# inputs.net
KiCad netlist of a schematic drawn in Altium Designer
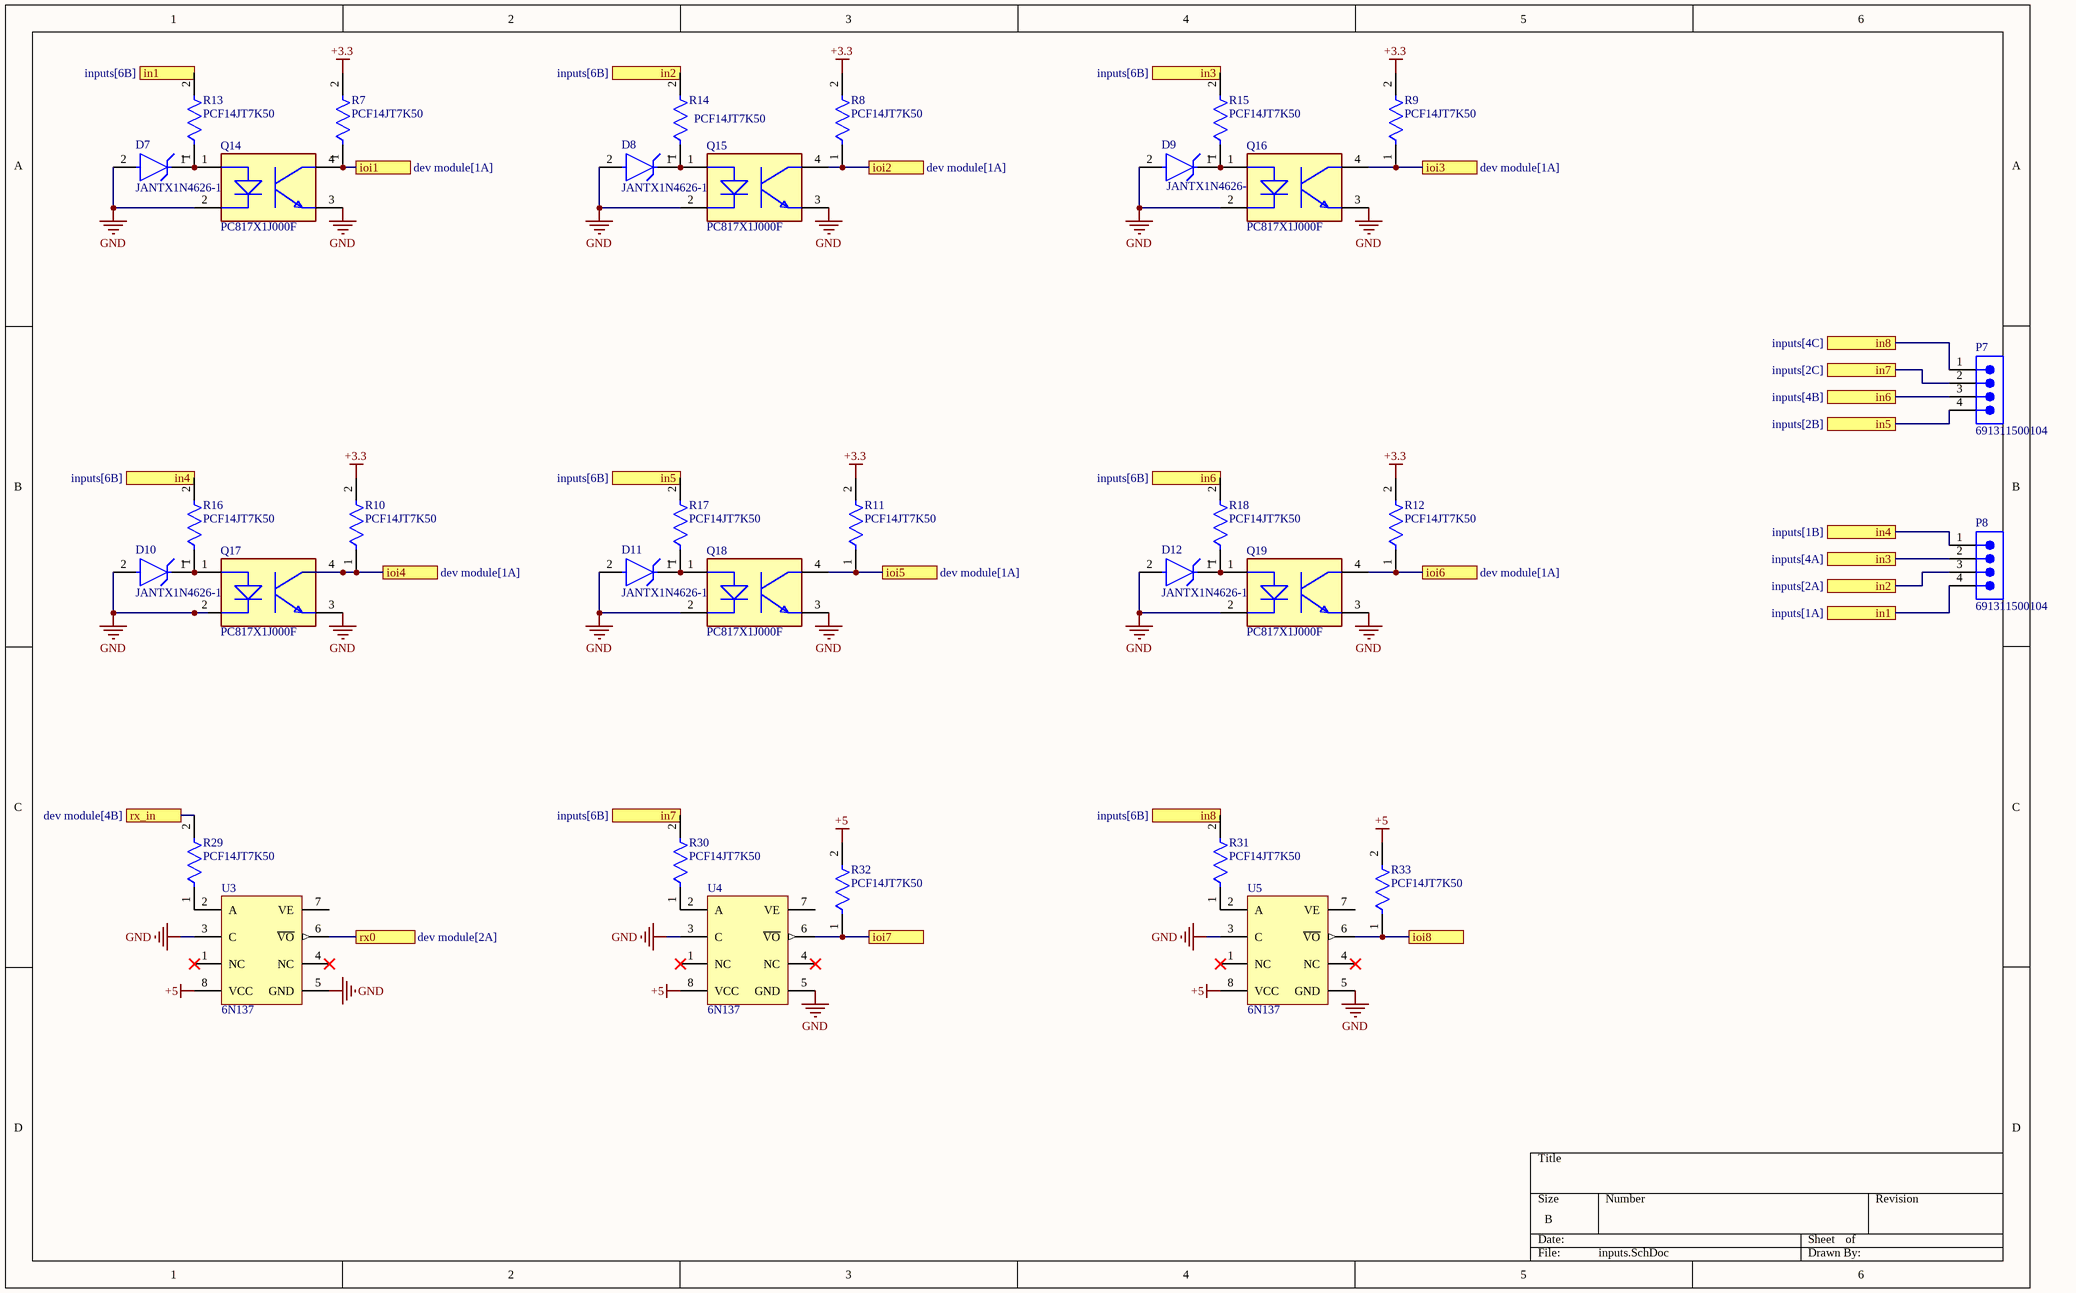
[diagram p0: inputs.SchDoc]

(export (version "E")
  (design (tool "Eeschema 10.0.6"))
  (components
    (comp (ref "D7")
      (value "JANTX1N4626-1")
      (footprint "FP-DO-35-MFG")
      (description "JANTX1N4626-1 Metallurgically Bonded Glass Zener Diode 5.6V 500mW 5% 2-Pin DO-204AH")
      (fields (field (name "TOLERANCE") "5%"))
      (libsource (lib "Altium Content Vault") (part "f813f71cba58e380607f5dd3caf9714"))
    )
    (comp (ref "D8")
      (value "JANTX1N4626-1")
      (footprint "FP-DO-35-MFG")
      (description "JANTX1N4626-1 Metallurgically Bonded Glass Zener Diode 5.6V 500mW 5% 2-Pin DO-204AH")
      (fields (field (name "TOLERANCE") "5%"))
      (libsource (lib "Altium Content Vault") (part "f813f71cba58e380607f5dd3caf9714"))
    )
    (comp (ref "D9")
      (value "JANTX1N4626-1")
      (footprint "FP-DO-35-MFG")
      (description "JANTX1N4626-1 Metallurgically Bonded Glass Zener Diode 5.6V 500mW 5% 2-Pin DO-204AH")
      (fields (field (name "TOLERANCE") "5%"))
      (libsource (lib "Altium Content Vault") (part "f813f71cba58e380607f5dd3caf9714"))
    )
    (comp (ref "D10")
      (value "JANTX1N4626-1")
      (footprint "FP-DO-35-MFG")
      (description "JANTX1N4626-1 Metallurgically Bonded Glass Zener Diode 5.6V 500mW 5% 2-Pin DO-204AH")
      (fields (field (name "TOLERANCE") "5%"))
      (libsource (lib "Altium Content Vault") (part "f813f71cba58e380607f5dd3caf9714"))
    )
    (comp (ref "D11")
      (value "JANTX1N4626-1")
      (footprint "FP-DO-35-MFG")
      (description "JANTX1N4626-1 Metallurgically Bonded Glass Zener Diode 5.6V 500mW 5% 2-Pin DO-204AH")
      (fields (field (name "TOLERANCE") "5%"))
      (libsource (lib "Altium Content Vault") (part "f813f71cba58e380607f5dd3caf9714"))
    )
    (comp (ref "D12")
      (value "JANTX1N4626-1")
      (footprint "FP-DO-35-MFG")
      (description "JANTX1N4626-1 Metallurgically Bonded Glass Zener Diode 5.6V 500mW 5% 2-Pin DO-204AH")
      (fields (field (name "TOLERANCE") "5%"))
      (libsource (lib "Altium Content Vault") (part "f813f71cba58e380607f5dd3caf9714"))
    )
    (comp (ref "P7")
      (value "691311500104")
      (footprint "691311500104")
      (fields (field (name "VOLTAGE") "300V"))
      (libsource (lib "Altium Content Vault") (part "TBL - 1R - 04P - Male"))
    )
    (comp (ref "P8")
      (value "691311500104")
      (footprint "691311500104")
      (fields (field (name "VOLTAGE") "300V"))
      (libsource (lib "Altium Content Vault") (part "TBL - 1R - 04P - Male"))
    )
    (comp (ref "Q14")
      (value "PC817X1J000F")
      (footprint "FP-PC817X1J000F-MFG")
      (description "OPTOISOLATOR 5KV TRANS 4DIP")
      (libsource (lib "Altium Content Vault") (part "8d9d817270a4e8f0d794346117f6aa3"))
    )
    (comp (ref "Q15")
      (value "PC817X1J000F")
      (footprint "FP-PC817X1J000F-MFG")
      (description "OPTOISOLATOR 5KV TRANS 4DIP")
      (libsource (lib "Altium Content Vault") (part "8d9d817270a4e8f0d794346117f6aa3"))
    )
    (comp (ref "Q16")
      (value "PC817X1J000F")
      (footprint "FP-PC817X1J000F-MFG")
      (description "OPTOISOLATOR 5KV TRANS 4DIP")
      (libsource (lib "Altium Content Vault") (part "8d9d817270a4e8f0d794346117f6aa3"))
    )
    (comp (ref "Q17")
      (value "PC817X1J000F")
      (footprint "FP-PC817X1J000F-MFG")
      (description "OPTOISOLATOR 5KV TRANS 4DIP")
      (libsource (lib "Altium Content Vault") (part "8d9d817270a4e8f0d794346117f6aa3"))
    )
    (comp (ref "Q18")
      (value "PC817X1J000F")
      (footprint "FP-PC817X1J000F-MFG")
      (description "OPTOISOLATOR 5KV TRANS 4DIP")
      (libsource (lib "Altium Content Vault") (part "8d9d817270a4e8f0d794346117f6aa3"))
    )
    (comp (ref "Q19")
      (value "PC817X1J000F")
      (footprint "FP-PC817X1J000F-MFG")
      (description "OPTOISOLATOR 5KV TRANS 4DIP")
      (libsource (lib "Altium Content Vault") (part "8d9d817270a4e8f0d794346117f6aa3"))
    )
    (comp (ref "R7")
      (value "PCF14JT7K50")
      (footprint "FP-CF14-MFG")
      (description "RES 7.5K OHM 1/4W 5% AXIAL")
      (fields (field (name "TOLERANCE") "5%"))
      (libsource (lib "Altium Content Vault") (part "1029c3af85768c4190bb7ad29bc67b5"))
    )
    (comp (ref "R8")
      (value "PCF14JT7K50")
      (footprint "FP-CF14-MFG")
      (description "RES 7.5K OHM 1/4W 5% AXIAL")
      (fields (field (name "TOLERANCE") "5%"))
      (libsource (lib "Altium Content Vault") (part "1029c3af85768c4190bb7ad29bc67b5"))
    )
    (comp (ref "R9")
      (value "PCF14JT7K50")
      (footprint "FP-CF14-MFG")
      (description "RES 7.5K OHM 1/4W 5% AXIAL")
      (fields (field (name "TOLERANCE") "5%"))
      (libsource (lib "Altium Content Vault") (part "1029c3af85768c4190bb7ad29bc67b5"))
    )
    (comp (ref "R10")
      (value "PCF14JT7K50")
      (footprint "FP-CF14-MFG")
      (description "RES 7.5K OHM 1/4W 5% AXIAL")
      (fields (field (name "TOLERANCE") "5%"))
      (libsource (lib "Altium Content Vault") (part "1029c3af85768c4190bb7ad29bc67b5"))
    )
    (comp (ref "R11")
      (value "PCF14JT7K50")
      (footprint "FP-CF14-MFG")
      (description "RES 7.5K OHM 1/4W 5% AXIAL")
      (fields (field (name "TOLERANCE") "5%"))
      (libsource (lib "Altium Content Vault") (part "1029c3af85768c4190bb7ad29bc67b5"))
    )
    (comp (ref "R12")
      (value "PCF14JT7K50")
      (footprint "FP-CF14-MFG")
      (description "RES 7.5K OHM 1/4W 5% AXIAL")
      (fields (field (name "TOLERANCE") "5%"))
      (libsource (lib "Altium Content Vault") (part "1029c3af85768c4190bb7ad29bc67b5"))
    )
    (comp (ref "R13")
      (value "PCF14JT7K50")
      (footprint "FP-CF14-MFG")
      (description "RES 7.5K OHM 1/4W 5% AXIAL")
      (fields (field (name "TOLERANCE") "5%"))
      (libsource (lib "Altium Content Vault") (part "1029c3af85768c4190bb7ad29bc67b5"))
    )
    (comp (ref "R14")
      (value "PCF14JT7K50")
      (footprint "FP-CF14-MFG")
      (description "RES 7.5K OHM 1/4W 5% AXIAL")
      (fields (field (name "TOLERANCE") "5%"))
      (libsource (lib "Altium Content Vault") (part "1029c3af85768c4190bb7ad29bc67b5"))
    )
    (comp (ref "R15")
      (value "PCF14JT7K50")
      (footprint "FP-CF14-MFG")
      (description "RES 7.5K OHM 1/4W 5% AXIAL")
      (fields (field (name "TOLERANCE") "5%"))
      (libsource (lib "Altium Content Vault") (part "1029c3af85768c4190bb7ad29bc67b5"))
    )
    (comp (ref "R16")
      (value "PCF14JT7K50")
      (footprint "FP-CF14-MFG")
      (description "RES 7.5K OHM 1/4W 5% AXIAL")
      (fields (field (name "TOLERANCE") "5%"))
      (libsource (lib "Altium Content Vault") (part "1029c3af85768c4190bb7ad29bc67b5"))
    )
    (comp (ref "R17")
      (value "PCF14JT7K50")
      (footprint "FP-CF14-MFG")
      (description "RES 7.5K OHM 1/4W 5% AXIAL")
      (fields (field (name "TOLERANCE") "5%"))
      (libsource (lib "Altium Content Vault") (part "1029c3af85768c4190bb7ad29bc67b5"))
    )
    (comp (ref "R18")
      (value "PCF14JT7K50")
      (footprint "FP-CF14-MFG")
      (description "RES 7.5K OHM 1/4W 5% AXIAL")
      (fields (field (name "TOLERANCE") "5%"))
      (libsource (lib "Altium Content Vault") (part "1029c3af85768c4190bb7ad29bc67b5"))
    )
    (comp (ref "R29")
      (value "PCF14JT7K50")
      (footprint "FP-CF14-MFG")
      (description "RES 7.5K OHM 1/4W 5% AXIAL")
      (fields (field (name "TOLERANCE") "5%"))
      (libsource (lib "Altium Content Vault") (part "1029c3af85768c4190bb7ad29bc67b5"))
    )
    (comp (ref "R30")
      (value "PCF14JT7K50")
      (footprint "FP-CF14-MFG")
      (description "RES 7.5K OHM 1/4W 5% AXIAL")
      (fields (field (name "TOLERANCE") "5%"))
      (libsource (lib "Altium Content Vault") (part "1029c3af85768c4190bb7ad29bc67b5"))
    )
    (comp (ref "R31")
      (value "PCF14JT7K50")
      (footprint "FP-CF14-MFG")
      (description "RES 7.5K OHM 1/4W 5% AXIAL")
      (fields (field (name "TOLERANCE") "5%"))
      (libsource (lib "Altium Content Vault") (part "1029c3af85768c4190bb7ad29bc67b5"))
    )
    (comp (ref "R32")
      (value "PCF14JT7K50")
      (footprint "FP-CF14-MFG")
      (description "RES 7.5K OHM 1/4W 5% AXIAL")
      (fields (field (name "TOLERANCE") "5%"))
      (libsource (lib "Altium Content Vault") (part "1029c3af85768c4190bb7ad29bc67b5"))
    )
    (comp (ref "R33")
      (value "PCF14JT7K50")
      (footprint "FP-CF14-MFG")
      (description "RES 7.5K OHM 1/4W 5% AXIAL")
      (fields (field (name "TOLERANCE") "5%"))
      (libsource (lib "Altium Content Vault") (part "1029c3af85768c4190bb7ad29bc67b5"))
    )
    (comp (ref "U3")
      (value "6N137")
      (footprint "VISH-DIP-8_A")
      (description "High Speed Optocoupler, Single and Dual, 10 MBd, 5 V, -40 to 100 degC, 8-Pin DIP, RoHS, Tube")
      (fields (field (name "MANUFACTURER") "Vishay"))
      (libsource (lib "Altium Content Vault") (part "VISH-6N137-DIP-8"))
    )
    (comp (ref "U4")
      (value "6N137")
      (footprint "VISH-DIP-8_A")
      (description "High Speed Optocoupler, Single and Dual, 10 MBd, 5 V, -40 to 100 degC, 8-Pin DIP, RoHS, Tube")
      (fields (field (name "MANUFACTURER") "Vishay"))
      (libsource (lib "Altium Content Vault") (part "VISH-6N137-DIP-8"))
    )
    (comp (ref "U5")
      (value "6N137")
      (footprint "VISH-DIP-8_A")
      (description "High Speed Optocoupler, Single and Dual, 10 MBd, 5 V, -40 to 100 degC, 8-Pin DIP, RoHS, Tube")
      (fields (field (name "MANUFACTURER") "Vishay"))
      (libsource (lib "Altium Content Vault") (part "VISH-6N137-DIP-8"))
    )
  )
  (nets
    (net (code "1") (name "+3.3") (class "Default")
      (node (ref "R10") (pin "2") (pinfunction "2_2") (pintype "passive"))
      (node (ref "R11") (pin "2") (pinfunction "2_2") (pintype "passive"))
      (node (ref "R12") (pin "2") (pinfunction "2_2") (pintype "passive"))
      (node (ref "R7") (pin "2") (pinfunction "2_2") (pintype "passive"))
      (node (ref "R8") (pin "2") (pinfunction "2_2") (pintype "passive"))
      (node (ref "R9") (pin "2") (pinfunction "2_2") (pintype "passive"))
    )
    (net (code "2") (name "+5") (class "Default")
      (node (ref "R32") (pin "2") (pinfunction "2_2") (pintype "passive"))
      (node (ref "R33") (pin "2") (pinfunction "2_2") (pintype "passive"))
      (node (ref "U3") (pin "8") (pinfunction "VCC_8") (pintype "power_in"))
      (node (ref "U4") (pin "8") (pinfunction "VCC_8") (pintype "power_in"))
      (node (ref "U5") (pin "8") (pinfunction "VCC_8") (pintype "power_in"))
    )
    (net (code "3") (name "/in1") (class "Default")
      (node (ref "P8") (pin "4") (pinfunction "4_4") (pintype "passive"))
      (node (ref "R13") (pin "2") (pinfunction "2_2") (pintype "passive"))
    )
    (net (code "4") (name "/in2") (class "Default")
      (node (ref "P8") (pin "3") (pinfunction "3_3") (pintype "passive"))
      (node (ref "R14") (pin "2") (pinfunction "2_2") (pintype "passive"))
    )
    (net (code "5") (name "/in3") (class "Default")
      (node (ref "P8") (pin "2") (pinfunction "2_2") (pintype "passive"))
      (node (ref "R15") (pin "2") (pinfunction "2_2") (pintype "passive"))
    )
    (net (code "6") (name "/in4") (class "Default")
      (node (ref "P8") (pin "1") (pinfunction "1_1") (pintype "passive"))
      (node (ref "R16") (pin "2") (pinfunction "2_2") (pintype "passive"))
    )
    (net (code "7") (name "/in5") (class "Default")
      (node (ref "P7") (pin "4") (pinfunction "4_4") (pintype "passive"))
      (node (ref "R17") (pin "2") (pinfunction "2_2") (pintype "passive"))
    )
    (net (code "8") (name "/in6") (class "Default")
      (node (ref "P7") (pin "3") (pinfunction "3_3") (pintype "passive"))
      (node (ref "R18") (pin "2") (pinfunction "2_2") (pintype "passive"))
    )
    (net (code "9") (name "/in7") (class "Default")
      (node (ref "P7") (pin "2") (pinfunction "2_2") (pintype "passive"))
      (node (ref "R30") (pin "2") (pinfunction "2_2") (pintype "passive"))
    )
    (net (code "10") (name "/in8") (class "Default")
      (node (ref "P7") (pin "1") (pinfunction "1_1") (pintype "passive"))
      (node (ref "R31") (pin "2") (pinfunction "2_2") (pintype "passive"))
    )
    (net (code "11") (name "/ioi1") (class "Default")
      (node (ref "Q14") (pin "4") (pinfunction "C_4") (pintype "passive"))
      (node (ref "R7") (pin "1") (pinfunction "1_1") (pintype "passive"))
    )
    (net (code "12") (name "/ioi2") (class "Default")
      (node (ref "Q15") (pin "4") (pinfunction "C_4") (pintype "passive"))
      (node (ref "R8") (pin "1") (pinfunction "1_1") (pintype "passive"))
    )
    (net (code "13") (name "/ioi3") (class "Default")
      (node (ref "Q16") (pin "4") (pinfunction "C_4") (pintype "passive"))
      (node (ref "R9") (pin "1") (pinfunction "1_1") (pintype "passive"))
    )
    (net (code "14") (name "/ioi4") (class "Default")
      (node (ref "Q17") (pin "4") (pinfunction "C_4") (pintype "passive"))
      (node (ref "R10") (pin "1") (pinfunction "1_1") (pintype "passive"))
    )
    (net (code "15") (name "/ioi5") (class "Default")
      (node (ref "Q18") (pin "4") (pinfunction "C_4") (pintype "passive"))
      (node (ref "R11") (pin "1") (pinfunction "1_1") (pintype "passive"))
    )
    (net (code "16") (name "/ioi6") (class "Default")
      (node (ref "Q19") (pin "4") (pinfunction "C_4") (pintype "passive"))
      (node (ref "R12") (pin "1") (pinfunction "1_1") (pintype "passive"))
    )
    (net (code "17") (name "/ioi7") (class "Default")
      (node (ref "R32") (pin "1") (pinfunction "1_1") (pintype "passive"))
      (node (ref "U4") (pin "6") (pinfunction "~{VO}_6") (pintype "output"))
    )
    (net (code "18") (name "/ioi8") (class "Default")
      (node (ref "R33") (pin "1") (pinfunction "1_1") (pintype "passive"))
      (node (ref "U5") (pin "6") (pinfunction "~{VO}_6") (pintype "output"))
    )
    (net (code "19") (name "/rx0") (class "Default")
      (node (ref "U3") (pin "6") (pinfunction "~{VO}_6") (pintype "output"))
    )
    (net (code "20") (name "/rx_in") (class "Default")
      (node (ref "R29") (pin "2") (pinfunction "2_2") (pintype "passive"))
    )
    (net (code "21") (name "GND") (class "Default")
      (node (ref "D10") (pin "2") (pinfunction "A_2") (pintype "passive"))
      (node (ref "D11") (pin "2") (pinfunction "A_2") (pintype "passive"))
      (node (ref "D12") (pin "2") (pinfunction "A_2") (pintype "passive"))
      (node (ref "D7") (pin "2") (pinfunction "A_2") (pintype "passive"))
      (node (ref "D8") (pin "2") (pinfunction "A_2") (pintype "passive"))
      (node (ref "D9") (pin "2") (pinfunction "A_2") (pintype "passive"))
      (node (ref "Q14") (pin "2") (pinfunction "C_2") (pintype "passive"))
      (node (ref "Q14") (pin "3") (pinfunction "E_3") (pintype "passive"))
      (node (ref "Q15") (pin "2") (pinfunction "C_2") (pintype "passive"))
      (node (ref "Q15") (pin "3") (pinfunction "E_3") (pintype "passive"))
      (node (ref "Q16") (pin "2") (pinfunction "C_2") (pintype "passive"))
      (node (ref "Q16") (pin "3") (pinfunction "E_3") (pintype "passive"))
      (node (ref "Q17") (pin "2") (pinfunction "C_2") (pintype "passive"))
      (node (ref "Q17") (pin "3") (pinfunction "E_3") (pintype "passive"))
      (node (ref "Q18") (pin "2") (pinfunction "C_2") (pintype "passive"))
      (node (ref "Q18") (pin "3") (pinfunction "E_3") (pintype "passive"))
      (node (ref "Q19") (pin "2") (pinfunction "C_2") (pintype "passive"))
      (node (ref "Q19") (pin "3") (pinfunction "E_3") (pintype "passive"))
      (node (ref "U3") (pin "3") (pinfunction "C_3") (pintype "passive"))
      (node (ref "U3") (pin "5") (pinfunction "GND_5") (pintype "power_in"))
      (node (ref "U4") (pin "3") (pinfunction "C_3") (pintype "passive"))
      (node (ref "U4") (pin "5") (pinfunction "GND_5") (pintype "power_in"))
      (node (ref "U5") (pin "3") (pinfunction "C_3") (pintype "passive"))
      (node (ref "U5") (pin "5") (pinfunction "GND_5") (pintype "power_in"))
    )
    (net (code "22") (name "Net-(D7-C)") (class "Default")
      (node (ref "D7") (pin "1") (pinfunction "C_1") (pintype "passive"))
      (node (ref "Q14") (pin "1") (pinfunction "A_1") (pintype "passive"))
      (node (ref "R13") (pin "1") (pinfunction "1_1") (pintype "passive"))
    )
    (net (code "23") (name "Net-(D8-C)") (class "Default")
      (node (ref "D8") (pin "1") (pinfunction "C_1") (pintype "passive"))
      (node (ref "Q15") (pin "1") (pinfunction "A_1") (pintype "passive"))
      (node (ref "R14") (pin "1") (pinfunction "1_1") (pintype "passive"))
    )
    (net (code "24") (name "Net-(D9-C)") (class "Default")
      (node (ref "D9") (pin "1") (pinfunction "C_1") (pintype "passive"))
      (node (ref "Q16") (pin "1") (pinfunction "A_1") (pintype "passive"))
      (node (ref "R15") (pin "1") (pinfunction "1_1") (pintype "passive"))
    )
    (net (code "25") (name "Net-(D10-C)") (class "Default")
      (node (ref "D10") (pin "1") (pinfunction "C_1") (pintype "passive"))
      (node (ref "Q17") (pin "1") (pinfunction "A_1") (pintype "passive"))
      (node (ref "R16") (pin "1") (pinfunction "1_1") (pintype "passive"))
    )
    (net (code "26") (name "Net-(D11-C)") (class "Default")
      (node (ref "D11") (pin "1") (pinfunction "C_1") (pintype "passive"))
      (node (ref "Q18") (pin "1") (pinfunction "A_1") (pintype "passive"))
      (node (ref "R17") (pin "1") (pinfunction "1_1") (pintype "passive"))
    )
    (net (code "27") (name "Net-(D12-C)") (class "Default")
      (node (ref "D12") (pin "1") (pinfunction "C_1") (pintype "passive"))
      (node (ref "Q19") (pin "1") (pinfunction "A_1") (pintype "passive"))
      (node (ref "R18") (pin "1") (pinfunction "1_1") (pintype "passive"))
    )
    (net (code "28") (name "Net-(U3-A)") (class "Default")
      (node (ref "R29") (pin "1") (pinfunction "1_1") (pintype "passive"))
      (node (ref "U3") (pin "2") (pinfunction "A_2") (pintype "passive"))
    )
    (net (code "29") (name "Net-(U4-A)") (class "Default")
      (node (ref "R30") (pin "1") (pinfunction "1_1") (pintype "passive"))
      (node (ref "U4") (pin "2") (pinfunction "A_2") (pintype "passive"))
    )
    (net (code "30") (name "Net-(U5-A)") (class "Default")
      (node (ref "R31") (pin "1") (pinfunction "1_1") (pintype "passive"))
      (node (ref "U5") (pin "2") (pinfunction "A_2") (pintype "passive"))
    )
    (net (code "31") (name "unconnected-(U3-NC-Pad1)") (class "Default")
      (node (ref "U3") (pin "1") (pinfunction "NC_1") (pintype "passive+no_connect"))
    )
    (net (code "32") (name "unconnected-(U3-NC-Pad4)") (class "Default")
      (node (ref "U3") (pin "4") (pinfunction "NC_4") (pintype "passive+no_connect"))
    )
    (net (code "33") (name "unconnected-(U3-VE-Pad7)") (class "Default")
      (node (ref "U3") (pin "7") (pinfunction "VE_7") (pintype "power_in"))
    )
    (net (code "34") (name "unconnected-(U4-NC-Pad1)") (class "Default")
      (node (ref "U4") (pin "1") (pinfunction "NC_1") (pintype "passive+no_connect"))
    )
    (net (code "35") (name "unconnected-(U4-NC-Pad4)") (class "Default")
      (node (ref "U4") (pin "4") (pinfunction "NC_4") (pintype "passive+no_connect"))
    )
    (net (code "36") (name "unconnected-(U4-VE-Pad7)") (class "Default")
      (node (ref "U4") (pin "7") (pinfunction "VE_7") (pintype "power_in"))
    )
    (net (code "37") (name "unconnected-(U5-NC-Pad1)") (class "Default")
      (node (ref "U5") (pin "1") (pinfunction "NC_1") (pintype "passive+no_connect"))
    )
    (net (code "38") (name "unconnected-(U5-NC-Pad4)") (class "Default")
      (node (ref "U5") (pin "4") (pinfunction "NC_4") (pintype "passive+no_connect"))
    )
    (net (code "39") (name "unconnected-(U5-VE-Pad7)") (class "Default")
      (node (ref "U5") (pin "7") (pinfunction "VE_7") (pintype "power_in"))
    )
  )
)
